# OPAMP_TESTER.net
KiCad netlist of a schematic drawn in Altium Designer
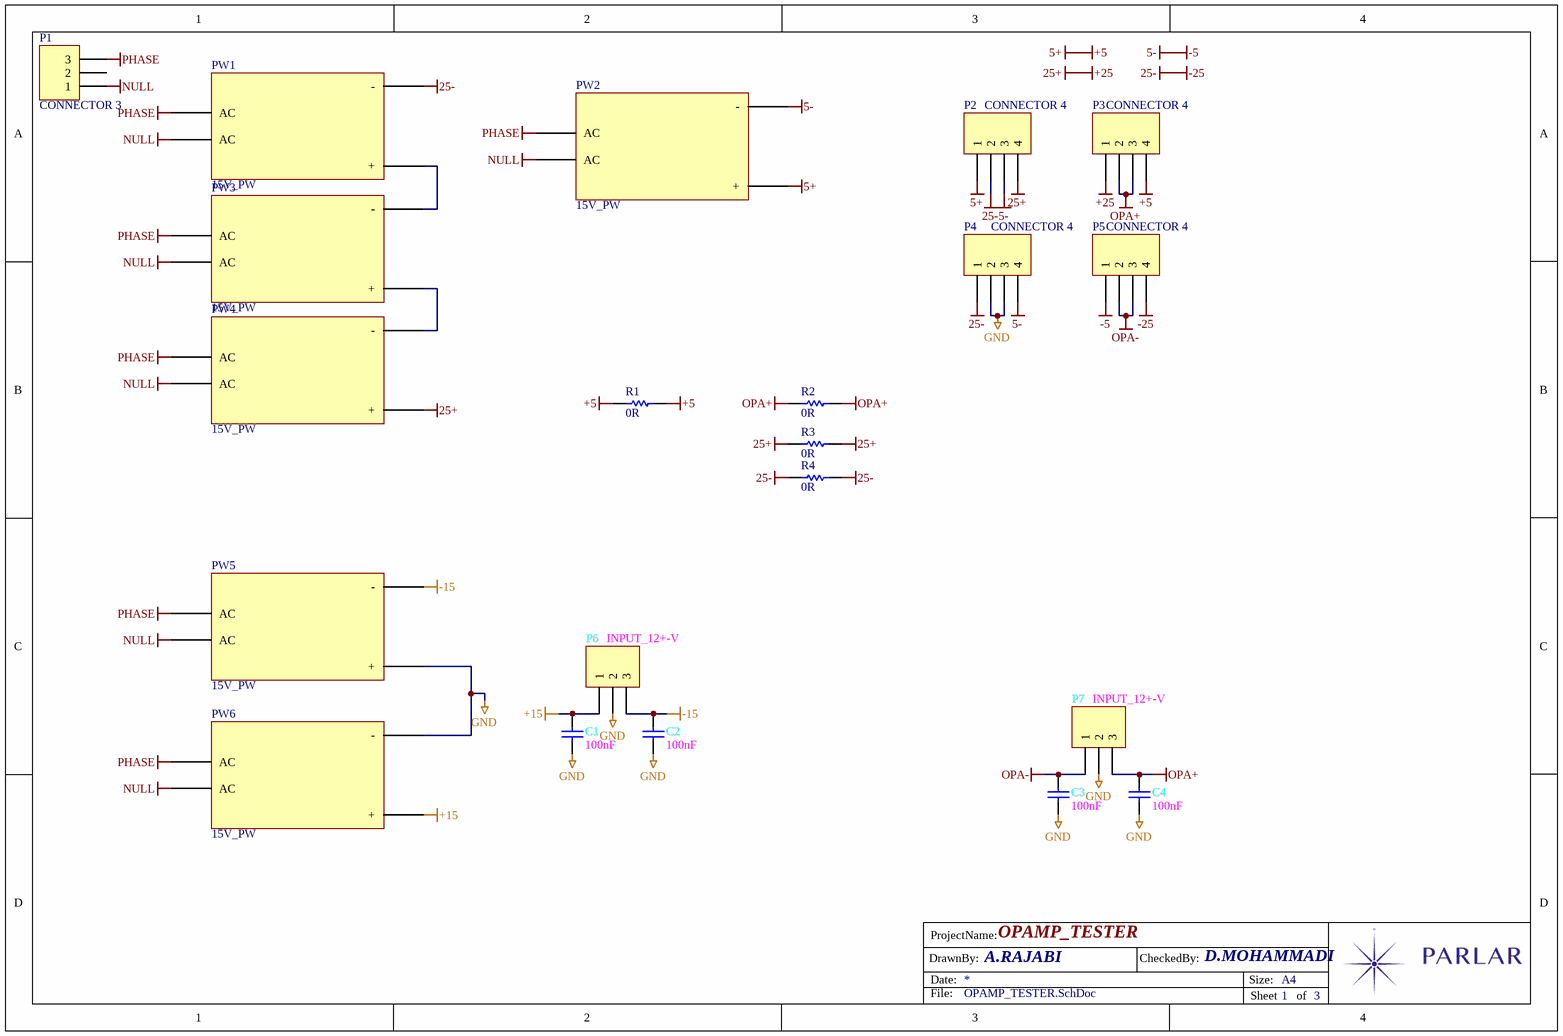
[diagram p0: OPAMP_TESTER.SchDoc]

(export (version "E")
  (design (tool "Eeschema 10.0.6"))
  (components
    (comp (ref "C1")
      (value "100nF")
      (footprint "SMD 0805")
      (description "Capacitor")
      (fields (field (name "PUBLISHER") "Altium Limited"))
      (libsource (lib "Parlarlib_30") (part "CAP"))
    )
    (comp (ref "C2")
      (value "100nF")
      (footprint "SMD 0805")
      (description "Capacitor")
      (fields (field (name "PUBLISHER") "Altium Limited"))
      (libsource (lib "Parlarlib_30") (part "CAP"))
    )
    (comp (ref "C3")
      (value "100nF")
      (footprint "SMD 0805")
      (description "Capacitor")
      (fields (field (name "PUBLISHER") "Altium Limited"))
      (libsource (lib "Parlarlib_30") (part "CAP"))
    )
    (comp (ref "C4")
      (value "100nF")
      (footprint "SMD 0805")
      (description "Capacitor")
      (fields (field (name "PUBLISHER") "Altium Limited"))
      (libsource (lib "Parlarlib_30") (part "CAP"))
    )
    (comp (ref "P1")
      (value "CONNECTOR 3")
      (footprint "CON VH 3")
      (description "Header, 3-Pin")
      (fields (field (name "PUBLISHER") "Altium Limited"))
      (libsource (lib "Parlarlib_33") (part "CONNECTOR 3"))
    )
    (comp (ref "P2")
      (value "CONNECTOR 4")
      (footprint "CON HDR 2.54M 4")
      (description "Header, 4-Pin")
      (fields (field (name "PUBLISHER") "Altium Limited"))
      (libsource (lib "Parlarlib_33") (part "CONNECTOR 4"))
    )
    (comp (ref "P3")
      (value "CONNECTOR 4")
      (footprint "CON HDR 2.54M 4")
      (description "Header, 4-Pin")
      (fields (field (name "PUBLISHER") "Altium Limited"))
      (libsource (lib "Parlarlib_33") (part "CONNECTOR 4"))
    )
    (comp (ref "P4")
      (value "CONNECTOR 4")
      (footprint "CON HDR 2.54M 4")
      (description "Header, 4-Pin")
      (fields (field (name "PUBLISHER") "Altium Limited"))
      (libsource (lib "Parlarlib_33") (part "CONNECTOR 4"))
    )
    (comp (ref "P5")
      (value "CONNECTOR 4")
      (footprint "CON HDR 2.54M 4")
      (description "Header, 4-Pin")
      (fields (field (name "PUBLISHER") "Altium Limited"))
      (libsource (lib "Parlarlib_33") (part "CONNECTOR 4"))
    )
    (comp (ref "P6")
      (value "INPUT_12+-V")
      (footprint "CON XH 3")
      (description "Header, 3-Pin")
      (fields (field (name "PUBLISHER") "Altium Limited"))
      (libsource (lib "Parlarlib_30") (part "CONNECTOR 3"))
    )
    (comp (ref "P7")
      (value "INPUT_12+-V")
      (footprint "CON XH 3")
      (description "Header, 3-Pin")
      (fields (field (name "PUBLISHER") "Altium Limited"))
      (libsource (lib "Parlarlib_30") (part "CONNECTOR 3"))
    )
    (comp (ref "PW1")
      (value "15V_PW")
      (footprint "POW_15V")
      (libsource (lib "SchlibPWANDKEY") (part "POWER"))
    )
    (comp (ref "PW2") (value "15V_PW") (footprint "POW_5V") (libsource (lib "SchlibPWANDKEY") (part "POWER")))
    (comp (ref "PW3") (value "15V_PW") (footprint "POW_5V") (libsource (lib "SchlibPWANDKEY") (part "POWER")))
    (comp (ref "PW4") (value "15V_PW") (footprint "POW_5V") (libsource (lib "SchlibPWANDKEY") (part "POWER")))
    (comp (ref "PW5")
      (value "15V_PW")
      (footprint "POW_15V")
      (libsource (lib "SchlibPWANDKEY") (part "POWER"))
    )
    (comp (ref "PW6")
      (value "15V_PW")
      (footprint "POW_15V")
      (libsource (lib "SchlibPWANDKEY") (part "POWER"))
    )
    (comp (ref "R1")
      (value "0R")
      (footprint "SMD 1206")
      (description "Resistor")
      (libsource (lib "Parlarlib_33") (part "RES"))
    )
    (comp (ref "R2")
      (value "0R")
      (footprint "SMD 1206")
      (description "Resistor")
      (libsource (lib "Parlarlib_33") (part "RES"))
    )
    (comp (ref "R3")
      (value "0R")
      (footprint "SMD 1206")
      (description "Resistor")
      (libsource (lib "Parlarlib_33") (part "RES"))
    )
    (comp (ref "R4")
      (value "0R")
      (footprint "SMD 1206")
      (description "Resistor")
      (libsource (lib "Parlarlib_33") (part "RES"))
    )
  )
  (nets
    (net (code "1") (name "+5") (class "Default")
      (node (ref "P2") (pin "1") (pinfunction "1_1") (pintype "passive"))
      (node (ref "P3") (pin "4") (pinfunction "4_4") (pintype "passive"))
      (node (ref "PW2") (pin "3") (pinfunction "+_3") (pintype "passive"))
      (node (ref "R1") (pin "1") (pinfunction "1_1") (pintype "passive"))
      (node (ref "R1") (pin "2") (pinfunction "2_2") (pintype "passive"))
    )
    (net (code "2") (name "+15") (class "Default")
      (node (ref "C1") (pin "2") (pinfunction "2_2") (pintype "passive"))
      (node (ref "P6") (pin "1") (pinfunction "1_1") (pintype "passive"))
      (node (ref "PW6") (pin "3") (pinfunction "+_3") (pintype "passive"))
    )
    (net (code "3") (name "+25") (class "Default")
      (node (ref "P2") (pin "4") (pinfunction "4_4") (pintype "passive"))
      (node (ref "P3") (pin "1") (pinfunction "1_1") (pintype "passive"))
      (node (ref "PW4") (pin "3") (pinfunction "+_3") (pintype "passive"))
      (node (ref "R3") (pin "1") (pinfunction "1_1") (pintype "passive"))
      (node (ref "R3") (pin "2") (pinfunction "2_2") (pintype "passive"))
    )
    (net (code "4") (name "-5") (class "Default")
      (node (ref "P2") (pin "3") (pinfunction "3_3") (pintype "passive"))
      (node (ref "P4") (pin "4") (pinfunction "4_4") (pintype "passive"))
      (node (ref "P5") (pin "1") (pinfunction "1_1") (pintype "passive"))
      (node (ref "PW2") (pin "4") (pinfunction "-_4") (pintype "passive"))
    )
    (net (code "5") (name "-15") (class "Default")
      (node (ref "C2") (pin "2") (pinfunction "2_2") (pintype "passive"))
      (node (ref "P6") (pin "3") (pinfunction "3_3") (pintype "passive"))
      (node (ref "PW5") (pin "4") (pinfunction "-_4") (pintype "passive"))
    )
    (net (code "6") (name "-25") (class "Default")
      (node (ref "P2") (pin "2") (pinfunction "2_2") (pintype "passive"))
      (node (ref "P4") (pin "1") (pinfunction "1_1") (pintype "passive"))
      (node (ref "P5") (pin "4") (pinfunction "4_4") (pintype "passive"))
      (node (ref "PW1") (pin "4") (pinfunction "-_4") (pintype "passive"))
      (node (ref "R4") (pin "1") (pinfunction "1_1") (pintype "passive"))
      (node (ref "R4") (pin "2") (pinfunction "2_2") (pintype "passive"))
    )
    (net (code "7") (name "GND") (class "Default")
      (node (ref "C1") (pin "1") (pinfunction "1_1") (pintype "passive"))
      (node (ref "C2") (pin "1") (pinfunction "1_1") (pintype "passive"))
      (node (ref "C3") (pin "1") (pinfunction "1_1") (pintype "passive"))
      (node (ref "C4") (pin "1") (pinfunction "1_1") (pintype "passive"))
      (node (ref "P4") (pin "2") (pinfunction "2_2") (pintype "passive"))
      (node (ref "P4") (pin "3") (pinfunction "3_3") (pintype "passive"))
      (node (ref "P6") (pin "2") (pinfunction "2_2") (pintype "passive"))
      (node (ref "P7") (pin "2") (pinfunction "2_2") (pintype "passive"))
      (node (ref "PW5") (pin "3") (pinfunction "+_3") (pintype "passive"))
      (node (ref "PW6") (pin "4") (pinfunction "-_4") (pintype "passive"))
    )
    (net (code "8") (name "NULL") (class "Default")
      (node (ref "P1") (pin "1") (pinfunction "1_1") (pintype "passive"))
      (node (ref "PW1") (pin "2") (pinfunction "AC_2") (pintype "passive"))
      (node (ref "PW2") (pin "2") (pinfunction "AC_2") (pintype "passive"))
      (node (ref "PW3") (pin "2") (pinfunction "AC_2") (pintype "passive"))
      (node (ref "PW4") (pin "2") (pinfunction "AC_2") (pintype "passive"))
      (node (ref "PW5") (pin "2") (pinfunction "AC_2") (pintype "passive"))
      (node (ref "PW6") (pin "2") (pinfunction "AC_2") (pintype "passive"))
    )
    (net (code "9") (name "Net-(PW1-+)") (class "Default")
      (node (ref "PW1") (pin "3") (pinfunction "+_3") (pintype "passive"))
      (node (ref "PW3") (pin "4") (pinfunction "-_4") (pintype "passive"))
    )
    (net (code "10") (name "Net-(PW3-+)") (class "Default")
      (node (ref "PW3") (pin "3") (pinfunction "+_3") (pintype "passive"))
      (node (ref "PW4") (pin "4") (pinfunction "-_4") (pintype "passive"))
    )
    (net (code "11") (name "OPA+") (class "Default")
      (node (ref "C4") (pin "2") (pinfunction "2_2") (pintype "passive"))
      (node (ref "P3") (pin "2") (pinfunction "2_2") (pintype "passive"))
      (node (ref "P3") (pin "3") (pinfunction "3_3") (pintype "passive"))
      (node (ref "P7") (pin "3") (pinfunction "3_3") (pintype "passive"))
      (node (ref "R2") (pin "1") (pinfunction "1_1") (pintype "passive"))
      (node (ref "R2") (pin "2") (pinfunction "2_2") (pintype "passive"))
    )
    (net (code "12") (name "OPA-") (class "Default")
      (node (ref "C3") (pin "2") (pinfunction "2_2") (pintype "passive"))
      (node (ref "P5") (pin "2") (pinfunction "2_2") (pintype "passive"))
      (node (ref "P5") (pin "3") (pinfunction "3_3") (pintype "passive"))
      (node (ref "P7") (pin "1") (pinfunction "1_1") (pintype "passive"))
    )
    (net (code "13") (name "PHASE") (class "Default")
      (node (ref "P1") (pin "3") (pinfunction "3_3") (pintype "passive"))
      (node (ref "PW1") (pin "1") (pinfunction "AC_1") (pintype "passive"))
      (node (ref "PW2") (pin "1") (pinfunction "AC_1") (pintype "passive"))
      (node (ref "PW3") (pin "1") (pinfunction "AC_1") (pintype "passive"))
      (node (ref "PW4") (pin "1") (pinfunction "AC_1") (pintype "passive"))
      (node (ref "PW5") (pin "1") (pinfunction "AC_1") (pintype "passive"))
      (node (ref "PW6") (pin "1") (pinfunction "AC_1") (pintype "passive"))
    )
    (net (code "14") (name "unconnected-(P1-Pad2)") (class "Default")
      (node (ref "P1") (pin "2") (pinfunction "2_2") (pintype "passive"))
    )
  )
)
